# 08_Peripherals.net
KiCad netlist of a schematic drawn in Altium Designer
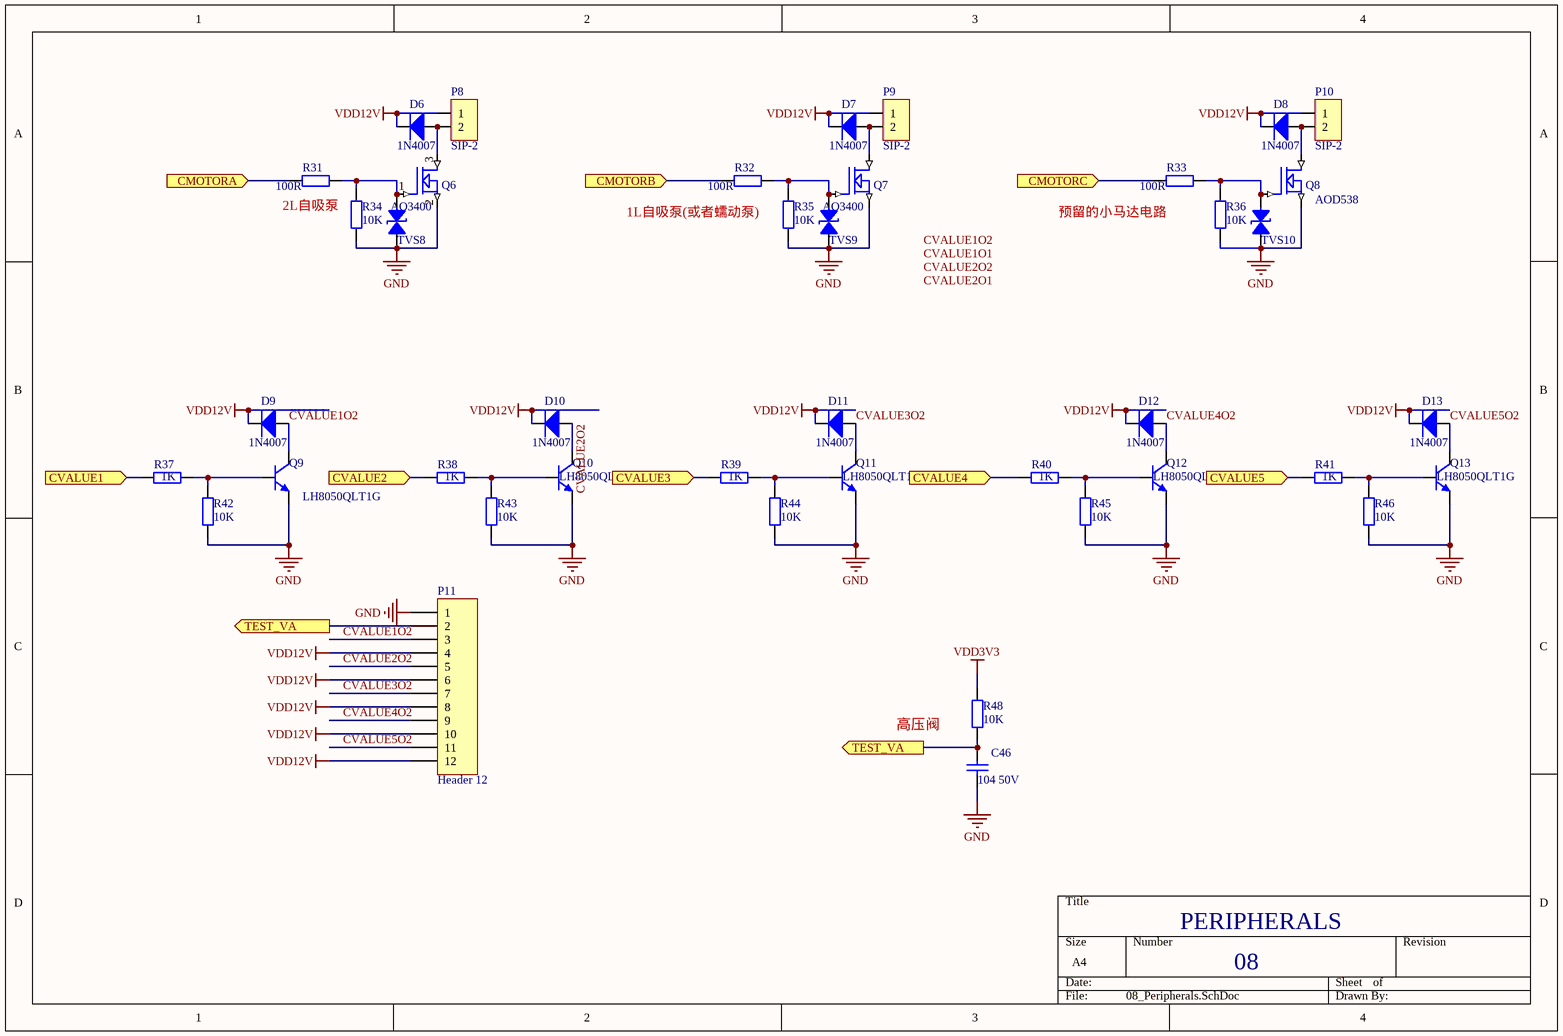
[diagram p0: 08_Peripherals.SchDoc]

(export (version "E")
  (design (tool "Eeschema 10.0.6"))
  (components
    (comp (ref "C46")
      (value "104 50V")
      (footprint "SMD-0603C")
      (description "贴片电容 10%")
      (libsource (lib "XiaoyI") (part "CAP4"))
    )
    (comp (ref "D6")
      (value "1N4007")
      (footprint "DO-214-AC")
      (description "贴片二极管")
      (libsource (lib "XiaoyI") (part "DIODE2"))
    )
    (comp (ref "D7")
      (value "1N4007")
      (footprint "DO-214-AC")
      (description "贴片二极管")
      (libsource (lib "XiaoyI") (part "DIODE2"))
    )
    (comp (ref "D8")
      (value "1N4007")
      (footprint "DO-214-AC")
      (description "贴片二极管")
      (libsource (lib "XiaoyI") (part "DIODE2"))
    )
    (comp (ref "D9")
      (value "1N4007")
      (footprint "DO-214-AC")
      (description "贴片二极管")
      (libsource (lib "XiaoyI") (part "DIODE2"))
    )
    (comp (ref "D10")
      (value "1N4007")
      (footprint "DO-214-AC")
      (description "贴片二极管")
      (libsource (lib "XiaoyI") (part "DIODE2"))
    )
    (comp (ref "D11")
      (value "1N4007")
      (footprint "DO-214-AC")
      (description "贴片二极管")
      (libsource (lib "XiaoyI") (part "DIODE2"))
    )
    (comp (ref "D12")
      (value "1N4007")
      (footprint "DO-214-AC")
      (description "贴片二极管")
      (libsource (lib "XiaoyI") (part "DIODE2"))
    )
    (comp (ref "D13")
      (value "1N4007")
      (footprint "DO-214-AC")
      (description "贴片二极管")
      (libsource (lib "XiaoyI") (part "DIODE2"))
    )
    (comp (ref "P8")
      (value "SIP-2")
      (footprint "SIP-2A")
      (description "XH2.54 2P 立贴")
      (libsource (lib "XiaoyI") (part "SIP-2"))
    )
    (comp (ref "P9")
      (value "SIP-2")
      (footprint "SIP-2A")
      (description "XH2.54 2P 立贴")
      (libsource (lib "XiaoyI") (part "SIP-2"))
    )
    (comp (ref "P10")
      (value "SIP-2")
      (footprint "VH-AW-3.96*2P")
      (description "XH2.54 2P 立贴")
      (libsource (lib "XiaoyI") (part "SIP-2"))
    )
    (comp (ref "P11")
      (value "Header 12")
      (footprint "12X2.54MMZ")
      (description "Header, 12-Pin")
      (fields (field (name "PUBLISHER") "Altium Limited"))
      (libsource (lib "Miscellaneous Connectors") (part "Header 12"))
    )
    (comp (ref "Q6")
      (value "AO3400")
      (footprint "SOT-23")
      (description "MOSFET N")
      (libsource (lib "") (part "MOSFET N_1"))
    )
    (comp (ref "Q7")
      (value "AO3400")
      (footprint "SOT-23")
      (description "MOSFET N")
      (libsource (lib "XiaoyI") (part "MOSFET N"))
    )
    (comp (ref "Q8")
      (value "AOD538")
      (footprint "TO252")
      (description "MOSFET N")
      (libsource (lib "XiaoyI") (part "MOSFET N"))
    )
    (comp (ref "Q9")
      (value "LH8050QLT1G")
      (footprint "SOT-23")
      (description "三极管")
      (libsource (lib "XiaoyI") (part "NPN-1"))
    )
    (comp (ref "Q10")
      (value "LH8050QLT1G")
      (footprint "SOT-23")
      (description "三极管")
      (libsource (lib "XiaoyI") (part "NPN-1"))
    )
    (comp (ref "Q11")
      (value "LH8050QLT1G")
      (footprint "SOT-23")
      (description "三极管")
      (libsource (lib "XiaoyI") (part "NPN-1"))
    )
    (comp (ref "Q12")
      (value "LH8050QLT1G")
      (footprint "SOT-23")
      (description "三极管")
      (libsource (lib "XiaoyI") (part "NPN-1"))
    )
    (comp (ref "Q13")
      (value "LH8050QLT1G")
      (footprint "SOT-23")
      (description "三极管")
      (libsource (lib "XiaoyI") (part "NPN-1"))
    )
    (comp (ref "R31")
      (value "100R")
      (footprint "SMD-0603")
      (description "贴片电阻 5%")
      (libsource (lib "") (part "RES-SOP_1"))
    )
    (comp (ref "R32")
      (value "100R")
      (footprint "SMD-0603")
      (description "贴片电阻 5%")
      (libsource (lib "") (part "RES-SOP_1"))
    )
    (comp (ref "R33")
      (value "100R")
      (footprint "SMD-0603")
      (description "贴片电阻 5%")
      (libsource (lib "") (part "RES-SOP_1"))
    )
    (comp (ref "R34")
      (value "10K")
      (footprint "SMD-0603")
      (description "贴片电阻 5%")
      (libsource (lib "XiaoyI") (part "RES-SOP"))
    )
    (comp (ref "R35")
      (value "10K")
      (footprint "SMD-0603")
      (description "贴片电阻 5%")
      (libsource (lib "XiaoyI") (part "RES-SOP"))
    )
    (comp (ref "R36")
      (value "10K")
      (footprint "SMD-0603")
      (description "贴片电阻 5%")
      (libsource (lib "XiaoyI") (part "RES-SOP"))
    )
    (comp (ref "R37")
      (value "1K")
      (footprint "SMD-0603")
      (description "贴片电阻 5%")
      (libsource (lib "") (part "RES-SOP_1"))
    )
    (comp (ref "R38")
      (value "1K")
      (footprint "SMD-0603")
      (description "贴片电阻 5%")
      (libsource (lib "") (part "RES-SOP_1"))
    )
    (comp (ref "R39")
      (value "1K")
      (footprint "SMD-0603")
      (description "贴片电阻 5%")
      (libsource (lib "") (part "RES-SOP_1"))
    )
    (comp (ref "R40")
      (value "1K")
      (footprint "SMD-0603")
      (description "贴片电阻 5%")
      (libsource (lib "") (part "RES-SOP_1"))
    )
    (comp (ref "R41")
      (value "1K")
      (footprint "SMD-0603")
      (description "贴片电阻 5%")
      (libsource (lib "") (part "RES-SOP_1"))
    )
    (comp (ref "R42")
      (value "10K")
      (footprint "SMD-0603")
      (description "贴片电阻 5%")
      (libsource (lib "XiaoyI") (part "RES-SOP"))
    )
    (comp (ref "R43")
      (value "10K")
      (footprint "SMD-0603")
      (description "贴片电阻 5%")
      (libsource (lib "XiaoyI") (part "RES-SOP"))
    )
    (comp (ref "R44")
      (value "10K")
      (footprint "SMD-0603")
      (description "贴片电阻 5%")
      (libsource (lib "XiaoyI") (part "RES-SOP"))
    )
    (comp (ref "R45")
      (value "10K")
      (footprint "SMD-0603")
      (description "贴片电阻 5%")
      (libsource (lib "XiaoyI") (part "RES-SOP"))
    )
    (comp (ref "R46")
      (value "10K")
      (footprint "SMD-0603")
      (description "贴片电阻 5%")
      (libsource (lib "XiaoyI") (part "RES-SOP"))
    )
    (comp (ref "R48")
      (value "10K")
      (footprint "SMD-0603")
      (description "贴片电阻 5%")
      (libsource (lib "") (part "RES-SOP_2"))
    )
    (comp (ref "TVS8")
      (value "ESD5Z5.0CT1G")
      (footprint "SOD-523")
      (description "TVS")
      (libsource (lib "XiaoyI") (part "TVS-1"))
    )
    (comp (ref "TVS9")
      (value "ESD5Z5.0CT1G")
      (footprint "SOD-523")
      (description "TVS")
      (libsource (lib "XiaoyI") (part "TVS-1"))
    )
    (comp (ref "TVS10")
      (value "ESD5Z5.0CT1G")
      (footprint "SOD-523")
      (description "TVS")
      (libsource (lib "XiaoyI") (part "TVS-1"))
    )
  )
  (nets
    (net (code "1") (name "/CMOTORA") (class "Default")
      (node (ref "R31") (pin "2") (pinfunction "2_2") (pintype "passive"))
    )
    (net (code "2") (name "/CMOTORB") (class "Default")
      (node (ref "R32") (pin "2") (pinfunction "2_2") (pintype "passive"))
    )
    (net (code "3") (name "/CMOTORC") (class "Default")
      (node (ref "R33") (pin "2") (pinfunction "2_2") (pintype "passive"))
    )
    (net (code "4") (name "/CVALUE1") (class "Default")
      (node (ref "R37") (pin "2") (pinfunction "2_2") (pintype "passive"))
    )
    (net (code "6") (name "/CVALUE1O2") (class "Default")
      (node (ref "D9") (pin "1") (pinfunction "A_1") (pintype "passive"))
      (node (ref "P11") (pin "3") (pinfunction "3_3") (pintype "passive"))
      (node (ref "Q9") (pin "3") (pinfunction "C_3") (pintype "passive"))
    )
    (net (code "7") (name "/CVALUE2") (class "Default")
      (node (ref "R38") (pin "2") (pinfunction "2_2") (pintype "passive"))
    )
    (net (code "9") (name "/CVALUE2O2") (class "Default")
      (node (ref "D10") (pin "1") (pinfunction "A_1") (pintype "passive"))
      (node (ref "P11") (pin "5") (pinfunction "5_5") (pintype "passive"))
      (node (ref "Q10") (pin "3") (pinfunction "C_3") (pintype "passive"))
    )
    (net (code "10") (name "/CVALUE3") (class "Default")
      (node (ref "R39") (pin "2") (pinfunction "2_2") (pintype "passive"))
    )
    (net (code "11") (name "/CVALUE3O2") (class "Default")
      (node (ref "D11") (pin "1") (pinfunction "A_1") (pintype "passive"))
      (node (ref "P11") (pin "7") (pinfunction "7_7") (pintype "passive"))
      (node (ref "Q11") (pin "3") (pinfunction "C_3") (pintype "passive"))
    )
    (net (code "12") (name "/CVALUE4") (class "Default")
      (node (ref "R40") (pin "2") (pinfunction "2_2") (pintype "passive"))
    )
    (net (code "13") (name "/CVALUE4O2") (class "Default")
      (node (ref "D12") (pin "1") (pinfunction "A_1") (pintype "passive"))
      (node (ref "P11") (pin "9") (pinfunction "9_9") (pintype "passive"))
      (node (ref "Q12") (pin "3") (pinfunction "C_3") (pintype "passive"))
    )
    (net (code "14") (name "/CVALUE5") (class "Default")
      (node (ref "R41") (pin "2") (pinfunction "2_2") (pintype "passive"))
    )
    (net (code "15") (name "/CVALUE5O2") (class "Default")
      (node (ref "D13") (pin "1") (pinfunction "A_1") (pintype "passive"))
      (node (ref "P11") (pin "11") (pinfunction "11_11") (pintype "passive"))
      (node (ref "Q13") (pin "3") (pinfunction "C_3") (pintype "passive"))
    )
    (net (code "16") (name "/TEST_VA") (class "Default")
      (node (ref "C46") (pin "2") (pinfunction "2_2") (pintype "passive"))
      (node (ref "P11") (pin "2") (pinfunction "2_2") (pintype "passive"))
      (node (ref "R48") (pin "1") (pinfunction "1_1") (pintype "passive"))
    )
    (net (code "17") (name "GND") (class "Default")
      (node (ref "C46") (pin "1") (pinfunction "1_1") (pintype "passive"))
      (node (ref "P11") (pin "1") (pinfunction "1_1") (pintype "passive"))
      (node (ref "Q10") (pin "2") (pinfunction "E_2") (pintype "passive"))
      (node (ref "Q11") (pin "2") (pinfunction "E_2") (pintype "passive"))
      (node (ref "Q12") (pin "2") (pinfunction "E_2") (pintype "passive"))
      (node (ref "Q13") (pin "2") (pinfunction "E_2") (pintype "passive"))
      (node (ref "Q6") (pin "2") (pinfunction "S_2") (pintype "output"))
      (node (ref "Q7") (pin "2") (pinfunction "S_2") (pintype "output"))
      (node (ref "Q8") (pin "2") (pinfunction "S_2") (pintype "output"))
      (node (ref "Q9") (pin "2") (pinfunction "E_2") (pintype "passive"))
      (node (ref "R34") (pin "2") (pinfunction "2_2") (pintype "passive"))
      (node (ref "R35") (pin "2") (pinfunction "2_2") (pintype "passive"))
      (node (ref "R36") (pin "2") (pinfunction "2_2") (pintype "passive"))
      (node (ref "R42") (pin "2") (pinfunction "2_2") (pintype "passive"))
      (node (ref "R43") (pin "2") (pinfunction "2_2") (pintype "passive"))
      (node (ref "R44") (pin "2") (pinfunction "2_2") (pintype "passive"))
      (node (ref "R45") (pin "2") (pinfunction "2_2") (pintype "passive"))
      (node (ref "R46") (pin "2") (pinfunction "2_2") (pintype "passive"))
      (node (ref "TVS10") (pin "1") (pinfunction "A_1") (pintype "passive"))
      (node (ref "TVS8") (pin "1") (pinfunction "A_1") (pintype "passive"))
      (node (ref "TVS9") (pin "1") (pinfunction "A_1") (pintype "passive"))
    )
    (net (code "18") (name "Net-(D6-A)") (class "Default")
      (node (ref "D6") (pin "1") (pinfunction "A_1") (pintype "passive"))
      (node (ref "P8") (pin "2") (pinfunction "2_2") (pintype "passive"))
      (node (ref "Q6") (pin "3") (pinfunction "D_3") (pintype "input"))
    )
    (net (code "19") (name "Net-(D7-A)") (class "Default")
      (node (ref "D7") (pin "1") (pinfunction "A_1") (pintype "passive"))
      (node (ref "P9") (pin "2") (pinfunction "2_2") (pintype "passive"))
      (node (ref "Q7") (pin "3") (pinfunction "D_3") (pintype "input"))
    )
    (net (code "20") (name "Net-(D8-A)") (class "Default")
      (node (ref "D8") (pin "1") (pinfunction "A_1") (pintype "passive"))
      (node (ref "P10") (pin "2") (pinfunction "2_2") (pintype "passive"))
      (node (ref "Q8") (pin "3") (pinfunction "D_3") (pintype "input"))
    )
    (net (code "21") (name "Net-(Q6-G)") (class "Default")
      (node (ref "Q6") (pin "1") (pinfunction "G_1") (pintype "input"))
      (node (ref "R31") (pin "1") (pinfunction "1_1") (pintype "passive"))
      (node (ref "R34") (pin "1") (pinfunction "1_1") (pintype "passive"))
      (node (ref "TVS8") (pin "2") (pinfunction "B_2") (pintype "passive"))
    )
    (net (code "22") (name "Net-(Q7-G)") (class "Default")
      (node (ref "Q7") (pin "1") (pinfunction "G_1") (pintype "input"))
      (node (ref "R32") (pin "1") (pinfunction "1_1") (pintype "passive"))
      (node (ref "R35") (pin "1") (pinfunction "1_1") (pintype "passive"))
      (node (ref "TVS9") (pin "2") (pinfunction "B_2") (pintype "passive"))
    )
    (net (code "23") (name "Net-(Q8-G)") (class "Default")
      (node (ref "Q8") (pin "1") (pinfunction "G_1") (pintype "input"))
      (node (ref "R33") (pin "1") (pinfunction "1_1") (pintype "passive"))
      (node (ref "R36") (pin "1") (pinfunction "1_1") (pintype "passive"))
      (node (ref "TVS10") (pin "2") (pinfunction "B_2") (pintype "passive"))
    )
    (net (code "24") (name "Net-(Q9-B)") (class "Default")
      (node (ref "Q9") (pin "1") (pinfunction "B_1") (pintype "passive"))
      (node (ref "R37") (pin "1") (pinfunction "1_1") (pintype "passive"))
      (node (ref "R42") (pin "1") (pinfunction "1_1") (pintype "passive"))
    )
    (net (code "25") (name "Net-(Q10-B)") (class "Default")
      (node (ref "Q10") (pin "1") (pinfunction "B_1") (pintype "passive"))
      (node (ref "R38") (pin "1") (pinfunction "1_1") (pintype "passive"))
      (node (ref "R43") (pin "1") (pinfunction "1_1") (pintype "passive"))
    )
    (net (code "26") (name "Net-(Q11-B)") (class "Default")
      (node (ref "Q11") (pin "1") (pinfunction "B_1") (pintype "passive"))
      (node (ref "R39") (pin "1") (pinfunction "1_1") (pintype "passive"))
      (node (ref "R44") (pin "1") (pinfunction "1_1") (pintype "passive"))
    )
    (net (code "27") (name "Net-(Q12-B)") (class "Default")
      (node (ref "Q12") (pin "1") (pinfunction "B_1") (pintype "passive"))
      (node (ref "R40") (pin "1") (pinfunction "1_1") (pintype "passive"))
      (node (ref "R45") (pin "1") (pinfunction "1_1") (pintype "passive"))
    )
    (net (code "28") (name "Net-(Q13-B)") (class "Default")
      (node (ref "Q13") (pin "1") (pinfunction "B_1") (pintype "passive"))
      (node (ref "R41") (pin "1") (pinfunction "1_1") (pintype "passive"))
      (node (ref "R46") (pin "1") (pinfunction "1_1") (pintype "passive"))
    )
    (net (code "29") (name "VDD3V3") (class "Default")
      (node (ref "R48") (pin "2") (pinfunction "2_2") (pintype "passive"))
    )
    (net (code "30") (name "VDD12V") (class "Default")
      (node (ref "D10") (pin "2") (pinfunction "K_2") (pintype "passive"))
      (node (ref "D11") (pin "2") (pinfunction "K_2") (pintype "passive"))
      (node (ref "D12") (pin "2") (pinfunction "K_2") (pintype "passive"))
      (node (ref "D13") (pin "2") (pinfunction "K_2") (pintype "passive"))
      (node (ref "D6") (pin "2") (pinfunction "K_2") (pintype "passive"))
      (node (ref "D7") (pin "2") (pinfunction "K_2") (pintype "passive"))
      (node (ref "D8") (pin "2") (pinfunction "K_2") (pintype "passive"))
      (node (ref "D9") (pin "2") (pinfunction "K_2") (pintype "passive"))
      (node (ref "P10") (pin "1") (pinfunction "1_1") (pintype "passive"))
      (node (ref "P11") (pin "10") (pinfunction "10_10") (pintype "passive"))
      (node (ref "P11") (pin "12") (pinfunction "12_12") (pintype "passive"))
      (node (ref "P11") (pin "4") (pinfunction "4_4") (pintype "passive"))
      (node (ref "P11") (pin "6") (pinfunction "6_6") (pintype "passive"))
      (node (ref "P11") (pin "8") (pinfunction "8_8") (pintype "passive"))
      (node (ref "P8") (pin "1") (pinfunction "1_1") (pintype "passive"))
      (node (ref "P9") (pin "1") (pinfunction "1_1") (pintype "passive"))
    )
  )
)
